# PA1_Alim.net
KiCad netlist of a schematic drawn in Altium Designer
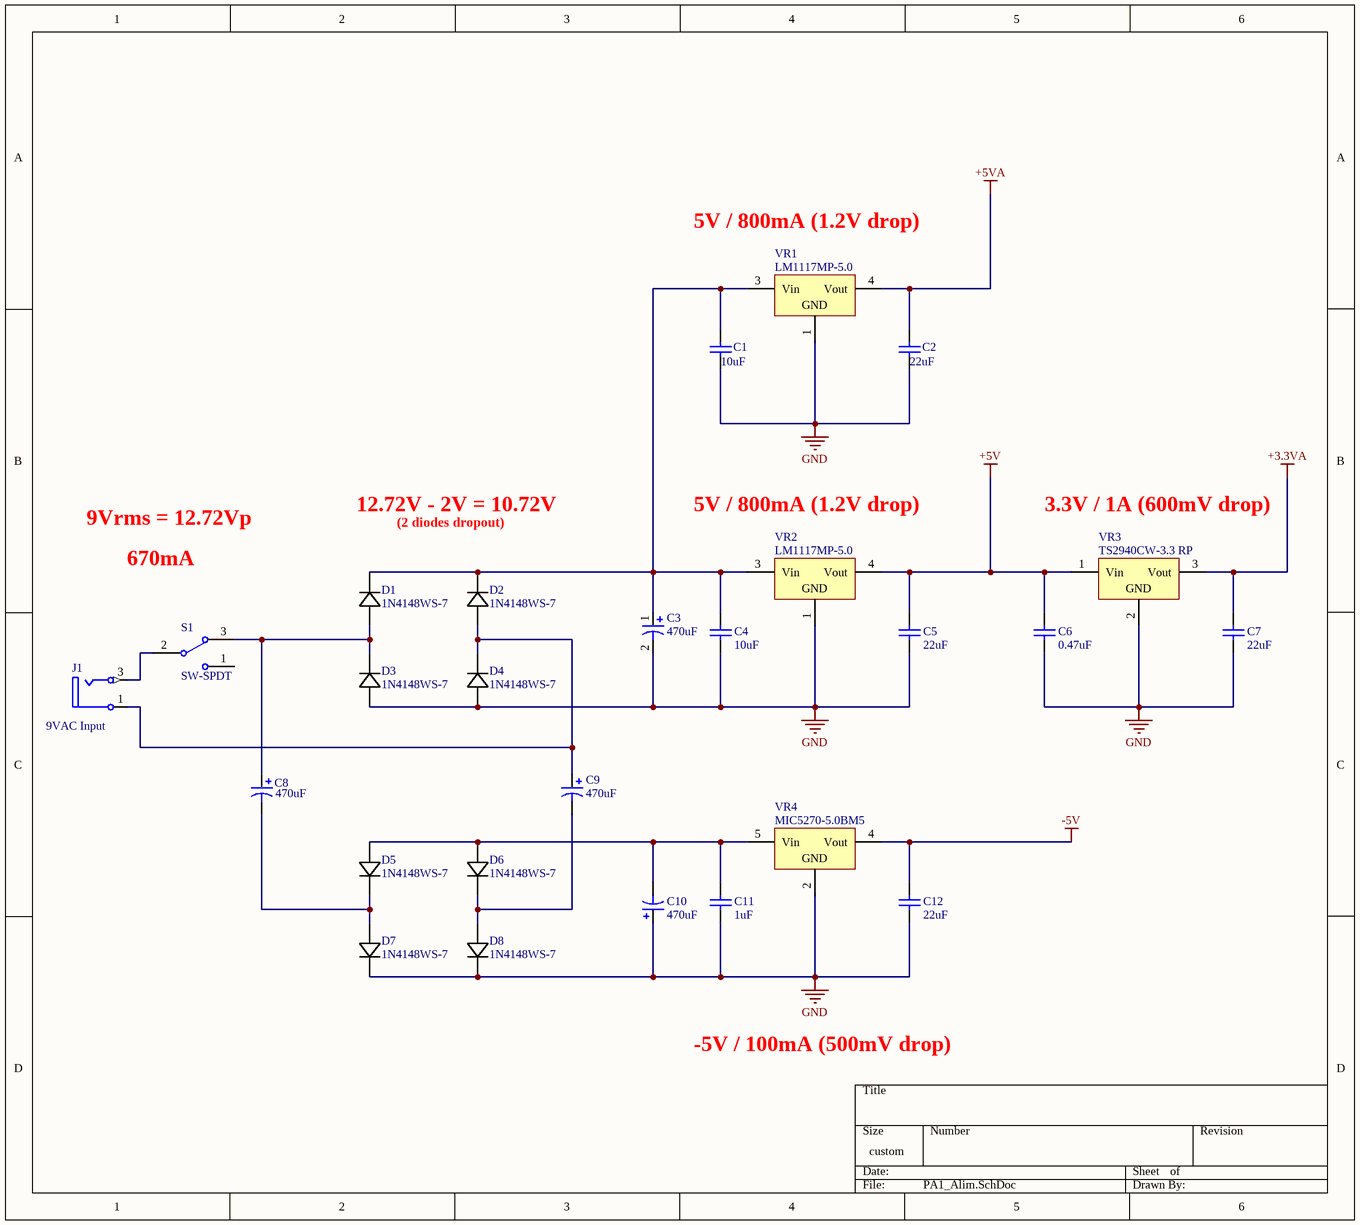
[diagram p0: PA1_Alim.SchDoc]

(export (version "E")
  (design (tool "Eeschema 10.0.6"))
  (components
    (comp (ref "C1")
      (value "10uF")
      (footprint "CAPC1608X08")
      (description "Capacitor")
      (fields (field (name "Comment") "Cap 10uF"))
      (libsource (lib "Michel") (part "Cap Semi"))
    )
    (comp (ref "C2")
      (value "22uF")
      (footprint "CAPC1608X08")
      (description "Capacitor")
      (fields (field (name "Comment") "Cap 22uF"))
      (libsource (lib "Michel") (part "Cap Semi"))
    )
    (comp (ref "C3")
      (value "470uF")
      (footprint "CAPC100100X102")
      (description "Polarized Capacitor (Radial)")
      (fields (field (name "Comment") "Cap 470uF"))
      (libsource (lib "") (part "Cap Pol1_1"))
    )
    (comp (ref "C4")
      (value "10uF")
      (footprint "CAPC1608X08")
      (description "Capacitor")
      (fields (field (name "Comment") "Cap 10uF"))
      (libsource (lib "Michel") (part "Cap Semi"))
    )
    (comp (ref "C5")
      (value "22uF")
      (footprint "CAPC1608X08")
      (description "Capacitor")
      (fields (field (name "Comment") "Cap 22uF"))
      (libsource (lib "Michel") (part "Cap Semi"))
    )
    (comp (ref "C6")
      (value "0.47uF")
      (footprint "CAPC1608X08")
      (description "Capacitor")
      (fields (field (name "Comment") "Cap 0.47uF"))
      (libsource (lib "Michel") (part "Cap Semi"))
    )
    (comp (ref "C7")
      (value "22uF")
      (footprint "CAPC1608X08")
      (description "Capacitor")
      (fields (field (name "Comment") "Cap 22uF"))
      (libsource (lib "Michel") (part "Cap Semi"))
    )
    (comp (ref "C8")
      (value "470uF")
      (footprint "CAPC100100X102")
      (description "Polarized Capacitor (Radial)")
      (fields (field (name "Comment") "Cap 470uF"))
      (libsource (lib "Michel") (part "Cap Pol1"))
    )
    (comp (ref "C9")
      (value "470uF")
      (footprint "CAPC100100X102")
      (description "Polarized Capacitor (Radial)")
      (fields (field (name "Comment") "Cap 470uF"))
      (libsource (lib "Michel") (part "Cap Pol1"))
    )
    (comp (ref "C10")
      (value "470uF")
      (footprint "CAPC100100X102")
      (description "Polarized Capacitor (Radial)")
      (fields (field (name "Comment") "Cap 470uF"))
      (libsource (lib "Michel") (part "Cap Pol1"))
    )
    (comp (ref "C11")
      (value "1uF")
      (footprint "CAPC1608X08")
      (description "Capacitor")
      (fields (field (name "Comment") "Cap 1uF"))
      (libsource (lib "Michel") (part "Cap Semi"))
    )
    (comp (ref "C12")
      (value "22uF")
      (footprint "CAPC1608X08")
      (description "Capacitor")
      (fields (field (name "Comment") "Cap 22uF"))
      (libsource (lib "Michel") (part "Cap Semi"))
    )
    (comp (ref "D1")
      (value "1N4148WS-7")
      (footprint "SOD323-M")
      (description "Diode signaux faibles")
      (libsource (lib "Michel") (part "1N4148WS-7"))
    )
    (comp (ref "D2")
      (value "1N4148WS-7")
      (footprint "SOD323-M")
      (description "Diode signaux faibles")
      (libsource (lib "Michel") (part "1N4148WS-7"))
    )
    (comp (ref "D3")
      (value "1N4148WS-7")
      (footprint "SOD323-M")
      (description "Diode signaux faibles")
      (libsource (lib "Michel") (part "1N4148WS-7"))
    )
    (comp (ref "D4")
      (value "1N4148WS-7")
      (footprint "SOD323-M")
      (description "Diode signaux faibles")
      (libsource (lib "Michel") (part "1N4148WS-7"))
    )
    (comp (ref "D5")
      (value "1N4148WS-7")
      (footprint "SOD323-M")
      (description "Diode signaux faibles")
      (libsource (lib "Michel") (part "1N4148WS-7"))
    )
    (comp (ref "D6")
      (value "1N4148WS-7")
      (footprint "SOD323-M")
      (description "Diode signaux faibles")
      (libsource (lib "Michel") (part "1N4148WS-7"))
    )
    (comp (ref "D7")
      (value "1N4148WS-7")
      (footprint "SOD323-M")
      (description "Diode signaux faibles")
      (libsource (lib "Michel") (part "1N4148WS-7"))
    )
    (comp (ref "D8")
      (value "1N4148WS-7")
      (footprint "SOD323-M")
      (description "Diode signaux faibles")
      (libsource (lib "Michel") (part "1N4148WS-7"))
    )
    (comp (ref "J1")
      (value "9VAC Input")
      (footprint "CLIFF ELECTRONIC COMPONENTS_FC681465P")
      (description "Jack Socket Thru-Hole Vertical 2-Conductor Open Circuit")
      (libsource (lib "Michel") (part "Phonejack2"))
    )
    (comp (ref "S1")
      (value "SW-SPDT")
      (footprint "C&K_TS01ABE")
      (description "SPDT Subminiature Toggle Switch, Right Angle Mounting, Vertical Actuation")
      (libsource (lib "Michel") (part "SW-SPDT"))
    )
    (comp (ref "VR1")
      (value "LM1117MP-5.0")
      (footprint "MP04A")
      (description "Voltage Regulator")
      (libsource (lib "") (part "Volt Reg_1"))
    )
    (comp (ref "VR2")
      (value "LM1117MP-5.0")
      (footprint "MP04A")
      (description "Voltage Regulator")
      (libsource (lib "") (part "Volt Reg_1"))
    )
    (comp (ref "VR3")
      (value "TS2940CW-3.3 RP")
      (footprint "SOT230P715X180-4N")
      (description "Voltage Regulator")
      (libsource (lib "Michel") (part "Volt Reg"))
    )
    (comp (ref "VR4")
      (value "MIC5270-5.0BM5")
      (footprint "SOT95P280X130-5N")
      (description "Voltage Regulator")
      (libsource (lib "") (part "Volt Reg_2"))
    )
  )
  (nets
    (net (code "1") (name "+3.3VA") (class "Default")
      (node (ref "C7") (pin "2") (pinfunction "2_2") (pintype "passive"))
      (node (ref "VR3") (pin "3") (pinfunction "Vout_3") (pintype "passive"))
    )
    (net (code "2") (name "+5V") (class "Default")
      (node (ref "C5") (pin "2") (pinfunction "2_2") (pintype "passive"))
      (node (ref "C6") (pin "2") (pinfunction "2_2") (pintype "passive"))
      (node (ref "VR2") (pin "4") (pinfunction "Vout_4") (pintype "passive"))
      (node (ref "VR3") (pin "1") (pinfunction "Vin_1") (pintype "passive"))
    )
    (net (code "3") (name "+5VA") (class "Default")
      (node (ref "C2") (pin "2") (pinfunction "2_2") (pintype "passive"))
      (node (ref "VR1") (pin "4") (pinfunction "Vout_4") (pintype "passive"))
    )
    (net (code "4") (name "-5V") (class "Default")
      (node (ref "C12") (pin "2") (pinfunction "2_2") (pintype "passive"))
      (node (ref "VR4") (pin "4") (pinfunction "Vout_4") (pintype "passive"))
    )
    (net (code "5") (name "GND") (class "Default")
      (node (ref "C1") (pin "1") (pinfunction "1_1") (pintype "passive"))
      (node (ref "C10") (pin "1") (pinfunction "1_1") (pintype "passive"))
      (node (ref "C11") (pin "1") (pinfunction "1_1") (pintype "passive"))
      (node (ref "C12") (pin "1") (pinfunction "1_1") (pintype "passive"))
      (node (ref "C2") (pin "1") (pinfunction "1_1") (pintype "passive"))
      (node (ref "C3") (pin "2") (pinfunction "2_2") (pintype "passive"))
      (node (ref "C4") (pin "1") (pinfunction "1_1") (pintype "passive"))
      (node (ref "C5") (pin "1") (pinfunction "1_1") (pintype "passive"))
      (node (ref "C6") (pin "1") (pinfunction "1_1") (pintype "passive"))
      (node (ref "C7") (pin "1") (pinfunction "1_1") (pintype "passive"))
      (node (ref "D3") (pin "2") (pinfunction "2_2") (pintype "passive"))
      (node (ref "D4") (pin "2") (pinfunction "2_2") (pintype "passive"))
      (node (ref "D7") (pin "1") (pinfunction "1_1") (pintype "passive"))
      (node (ref "D8") (pin "1") (pinfunction "1_1") (pintype "passive"))
      (node (ref "VR1") (pin "1") (pinfunction "GND_1") (pintype "passive"))
      (node (ref "VR2") (pin "1") (pinfunction "GND_1") (pintype "passive"))
      (node (ref "VR3") (pin "2") (pinfunction "GND_2") (pintype "passive"))
      (node (ref "VR4") (pin "2") (pinfunction "GND_2") (pintype "passive"))
    )
    (net (code "6") (name "Net-(C8-Pad1)") (class "Default")
      (node (ref "C8") (pin "1") (pinfunction "1_1") (pintype "passive"))
      (node (ref "D1") (pin "2") (pinfunction "2_2") (pintype "passive"))
      (node (ref "D3") (pin "1") (pinfunction "1_1") (pintype "passive"))
      (node (ref "S1") (pin "3") (pinfunction "3_3") (pintype "passive"))
    )
    (net (code "7") (name "Net-(C8-Pad2)") (class "Default")
      (node (ref "C8") (pin "2") (pinfunction "2_2") (pintype "passive"))
      (node (ref "D5") (pin "1") (pinfunction "1_1") (pintype "passive"))
      (node (ref "D7") (pin "2") (pinfunction "2_2") (pintype "passive"))
    )
    (net (code "8") (name "Net-(C9-Pad2)") (class "Default")
      (node (ref "C9") (pin "2") (pinfunction "2_2") (pintype "passive"))
      (node (ref "D6") (pin "1") (pinfunction "1_1") (pintype "passive"))
      (node (ref "D8") (pin "2") (pinfunction "2_2") (pintype "passive"))
    )
    (net (code "9") (name "Net-(J1-S)") (class "Default")
      (node (ref "C9") (pin "1") (pinfunction "1_1") (pintype "passive"))
      (node (ref "D2") (pin "2") (pinfunction "2_2") (pintype "passive"))
      (node (ref "D4") (pin "1") (pinfunction "1_1") (pintype "passive"))
      (node (ref "J1") (pin "1") (pinfunction "S_1") (pintype "power_in"))
    )
    (net (code "10") (name "Net-(J1-T)") (class "Default")
      (node (ref "J1") (pin "3") (pinfunction "T_3") (pintype "output"))
      (node (ref "S1") (pin "2") (pinfunction "2_2") (pintype "passive"))
    )
    (net (code "11") (name "Net-(VR1-Vin)") (class "Default")
      (node (ref "C1") (pin "2") (pinfunction "2_2") (pintype "passive"))
      (node (ref "C3") (pin "1") (pinfunction "1_1") (pintype "passive"))
      (node (ref "C4") (pin "2") (pinfunction "2_2") (pintype "passive"))
      (node (ref "D1") (pin "1") (pinfunction "1_1") (pintype "passive"))
      (node (ref "D2") (pin "1") (pinfunction "1_1") (pintype "passive"))
      (node (ref "VR1") (pin "3") (pinfunction "Vin_3") (pintype "passive"))
      (node (ref "VR2") (pin "3") (pinfunction "Vin_3") (pintype "passive"))
    )
    (net (code "12") (name "Net-(VR4-Vin)") (class "Default")
      (node (ref "C10") (pin "2") (pinfunction "2_2") (pintype "passive"))
      (node (ref "C11") (pin "2") (pinfunction "2_2") (pintype "passive"))
      (node (ref "D5") (pin "2") (pinfunction "2_2") (pintype "passive"))
      (node (ref "D6") (pin "2") (pinfunction "2_2") (pintype "passive"))
      (node (ref "VR4") (pin "5") (pinfunction "Vin_5") (pintype "passive"))
    )
    (net (code "13") (name "unconnected-(S1-Pad1)") (class "Default")
      (node (ref "S1") (pin "1") (pinfunction "1_1") (pintype "passive"))
    )
  )
)
